# PM_HDMI_CON.net
KiCad netlist of a schematic drawn in Altium Designer
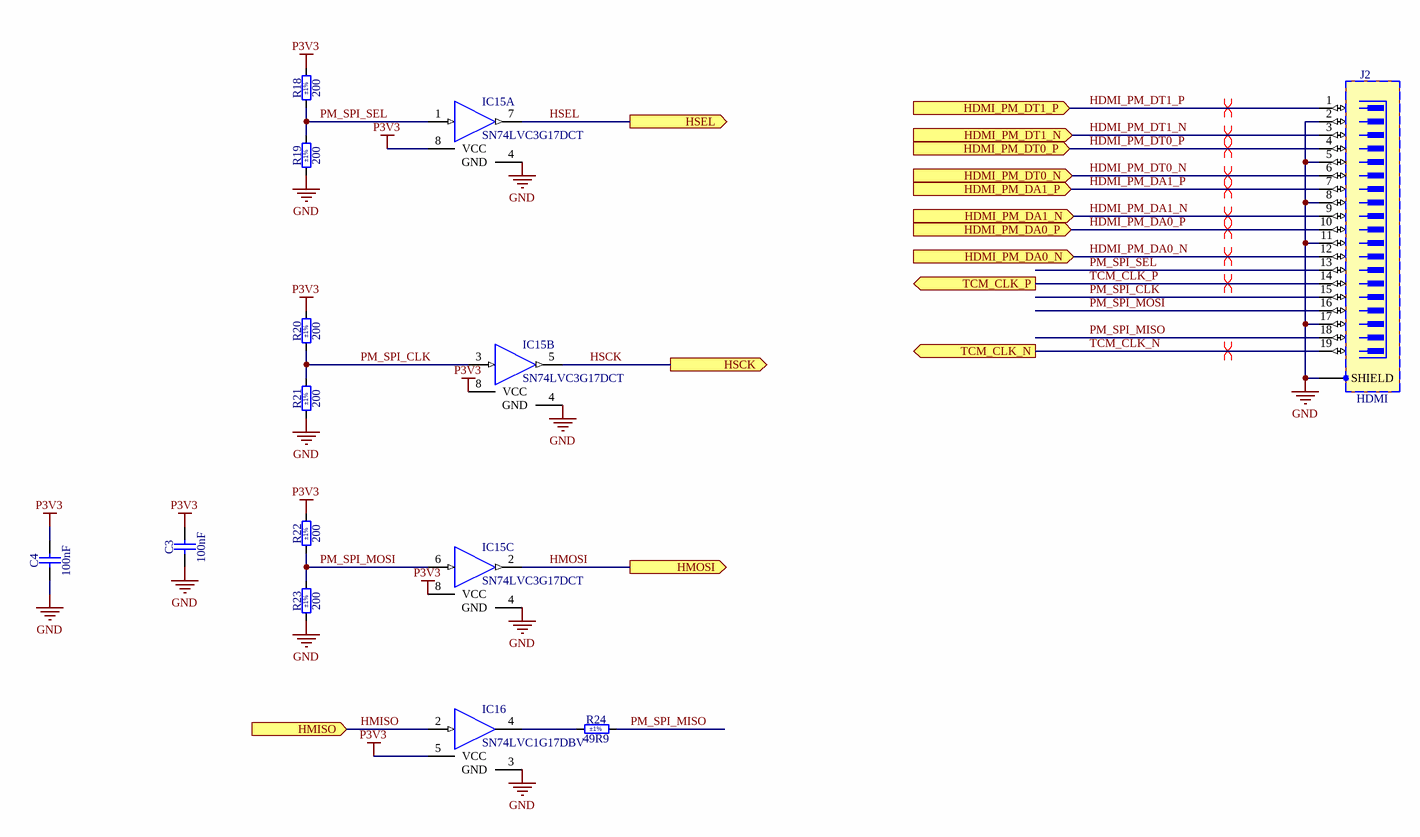
[diagram p0: PM_HDMI_CON.SchDoc]

(export (version "E")
  (design (tool "Eeschema 10.0.6"))
  (components
    (comp (ref "C3")
      (value "100nF")
      (footprint "CAPC1005X55N")
      (description "Non-polarised capacitor")
      (fields
        (field (name "PART NUMBER") "CC0402_100NF_50V_10%_X7R")
        (field (name "VOLTAGE") "50V")
        (field (name "AUTHOR") "CERN DEM MR")
      )
      (libsource (lib "Capacitors") (part "Capacitor - non polarized"))
    )
    (comp (ref "C4")
      (value "100nF")
      (footprint "CAPC1005X55N")
      (description "Non-polarised capacitor")
      (fields
        (field (name "PART NUMBER") "CC0402_100NF_50V_10%_X7R")
        (field (name "VOLTAGE") "50V")
        (field (name "AUTHOR") "CERN DEM MR")
      )
      (libsource (lib "Capacitors") (part "Capacitor - non polarized"))
    )
    (comp (ref "IC15")
      (value "SN74LVC3G17DCT")
      (footprint "SOP65P400X130-8N")
      (description "Triple Schmitt-Trigger Buffer")
      (fields (field (name "MANUFACTURER") "TEXAS INSTRUMENTS") (field (name "AUTHOR") "CERN DEM HF"))
      (libsource (lib "ICs And Semiconductors") (part "743G17"))
    )
    (comp (ref "IC16")
      (value "SN74LVC1G17DBV")
      (footprint "SOT95P280X145-5N")
      (description "Single Schmitt-Trigger Buffer")
      (fields
        (field (name "PART NUMBER") "SN74LVC1G17DBVR")
        (field (name "MANUFACTURER") "TEXAS INSTRUMENTS")
        (field (name "AUTHOR") "CERN DEM JLC")
      )
      (libsource (lib "ICs And Semiconductors") (part "741G17"))
    )
    (comp (ref "J2")
      (value "HDMI")
      (footprint "TYCO_2007435-1")
      (description "Connector HDMI 19 Male + 1 Shield")
      (fields
        (field (name "PART NUMBER") "TYCO_2007435-1")
        (field (name "MANUFACTURER") "TYCO ELECTRONICS")
        (field (name "AUTHOR") "CERN DEM MR")
      )
      (libsource (lib "Connectors") (part "Connector HDMI 19 Male + 1 Shield"))
    )
    (comp (ref "R18")
      (value "200")
      (footprint "RESC1608X55N")
      (description "Resistor - 1%")
      (fields
        (field (name "TOLERANCE") "±1%")
        (field (name "PART NUMBER") "R0603_200R_1%_0.1W_100PPM")
        (field (name "POWER") "0.1W")
        (field (name "AUTHOR") "CERN DEM JLC")
      )
      (libsource (lib "Resistors") (part "Resistor - 1%"))
    )
    (comp (ref "R19")
      (value "200")
      (footprint "RESC1608X55N")
      (description "Resistor - 1%")
      (fields
        (field (name "TOLERANCE") "±1%")
        (field (name "PART NUMBER") "R0603_200R_1%_0.1W_100PPM")
        (field (name "POWER") "0.1W")
        (field (name "AUTHOR") "CERN DEM JLC")
      )
      (libsource (lib "Resistors") (part "Resistor - 1%"))
    )
    (comp (ref "R20")
      (value "200")
      (footprint "RESC1608X55N")
      (description "Resistor - 1%")
      (fields
        (field (name "TOLERANCE") "±1%")
        (field (name "PART NUMBER") "R0603_200R_1%_0.1W_100PPM")
        (field (name "POWER") "0.1W")
        (field (name "AUTHOR") "CERN DEM JLC")
      )
      (libsource (lib "Resistors") (part "Resistor - 1%"))
    )
    (comp (ref "R21")
      (value "200")
      (footprint "RESC1608X55N")
      (description "Resistor - 1%")
      (fields
        (field (name "TOLERANCE") "±1%")
        (field (name "PART NUMBER") "R0603_200R_1%_0.1W_100PPM")
        (field (name "POWER") "0.1W")
        (field (name "AUTHOR") "CERN DEM JLC")
      )
      (libsource (lib "Resistors") (part "Resistor - 1%"))
    )
    (comp (ref "R22")
      (value "200")
      (footprint "RESC1608X55N")
      (description "Resistor - 1%")
      (fields
        (field (name "TOLERANCE") "±1%")
        (field (name "PART NUMBER") "R0603_200R_1%_0.1W_100PPM")
        (field (name "POWER") "0.1W")
        (field (name "AUTHOR") "CERN DEM JLC")
      )
      (libsource (lib "Resistors") (part "Resistor - 1%"))
    )
    (comp (ref "R23")
      (value "200")
      (footprint "RESC1608X55N")
      (description "Resistor - 1%")
      (fields
        (field (name "TOLERANCE") "±1%")
        (field (name "PART NUMBER") "R0603_200R_1%_0.1W_100PPM")
        (field (name "POWER") "0.1W")
        (field (name "AUTHOR") "CERN DEM JLC")
      )
      (libsource (lib "Resistors") (part "Resistor - 1%"))
    )
    (comp (ref "R24")
      (value "49R9")
      (footprint "RESC1005X40N")
      (description "Resistor - 1%")
      (fields
        (field (name "TOLERANCE") "±1%")
        (field (name "PART NUMBER") "R0402_49R9_1%_0.0625W_100PPM")
        (field (name "POWER") "0.0625W")
        (field (name "AUTHOR") "CERN DEM JLC")
      )
      (libsource (lib "Resistors") (part "Resistor - 1%"))
    )
  )
  (nets
    (net (code "1") (name "/HDMI_PM_DA0_N") (class "Default")
      (node (ref "J2") (pin "12") (pinfunction "12_12") (pintype "bidirectional"))
    )
    (net (code "2") (name "/HDMI_PM_DA0_P") (class "Default")
      (node (ref "J2") (pin "10") (pinfunction "10_10") (pintype "bidirectional"))
    )
    (net (code "3") (name "/HDMI_PM_DA1_N") (class "Default")
      (node (ref "J2") (pin "9") (pinfunction "9_9") (pintype "bidirectional"))
    )
    (net (code "4") (name "/HDMI_PM_DA1_P") (class "Default")
      (node (ref "J2") (pin "7") (pinfunction "7_7") (pintype "bidirectional"))
    )
    (net (code "5") (name "/HDMI_PM_DT0_N") (class "Default")
      (node (ref "J2") (pin "6") (pinfunction "6_6") (pintype "bidirectional"))
    )
    (net (code "6") (name "/HDMI_PM_DT0_P") (class "Default")
      (node (ref "J2") (pin "4") (pinfunction "4_4") (pintype "bidirectional"))
    )
    (net (code "7") (name "/HDMI_PM_DT1_N") (class "Default")
      (node (ref "J2") (pin "3") (pinfunction "3_3") (pintype "bidirectional"))
    )
    (net (code "8") (name "/HDMI_PM_DT1_P") (class "Default")
      (node (ref "J2") (pin "1") (pinfunction "1_1") (pintype "bidirectional"))
    )
    (net (code "9") (name "/HMISO") (class "Default")
      (node (ref "IC16") (pin "2") (pinfunction "IN_2") (pintype "input"))
    )
    (net (code "10") (name "/HMOSI") (class "Default")
      (node (ref "IC15") (pin "2") (pinfunction "OUT_2") (pintype "output"))
    )
    (net (code "11") (name "/HSCK") (class "Default")
      (node (ref "IC15") (pin "5") (pinfunction "OUT_5") (pintype "output"))
    )
    (net (code "12") (name "/HSEL") (class "Default")
      (node (ref "IC15") (pin "7") (pinfunction "OUT_7") (pintype "output"))
    )
    (net (code "13") (name "/PM_SPI_CLK") (class "Default")
      (node (ref "IC15") (pin "3") (pinfunction "IN_3") (pintype "input"))
      (node (ref "J2") (pin "15") (pinfunction "15_15") (pintype "bidirectional"))
      (node (ref "R20") (pin "1") (pinfunction "1_1") (pintype "passive"))
      (node (ref "R21") (pin "2") (pinfunction "2_2") (pintype "passive"))
    )
    (net (code "14") (name "/PM_SPI_MISO") (class "Default")
      (node (ref "J2") (pin "18") (pinfunction "18_18") (pintype "bidirectional"))
      (node (ref "R24") (pin "2") (pinfunction "2_2") (pintype "passive"))
    )
    (net (code "15") (name "/PM_SPI_MOSI") (class "Default")
      (node (ref "IC15") (pin "6") (pinfunction "IN_6") (pintype "input"))
      (node (ref "J2") (pin "16") (pinfunction "16_16") (pintype "bidirectional"))
      (node (ref "R22") (pin "1") (pinfunction "1_1") (pintype "passive"))
      (node (ref "R23") (pin "2") (pinfunction "2_2") (pintype "passive"))
    )
    (net (code "16") (name "/PM_SPI_SEL") (class "Default")
      (node (ref "IC15") (pin "1") (pinfunction "IN_1") (pintype "input"))
      (node (ref "J2") (pin "13") (pinfunction "13_13") (pintype "bidirectional"))
      (node (ref "R18") (pin "1") (pinfunction "1_1") (pintype "passive"))
      (node (ref "R19") (pin "2") (pinfunction "2_2") (pintype "passive"))
    )
    (net (code "17") (name "/TCM_CLK_N") (class "Default")
      (node (ref "J2") (pin "19") (pinfunction "19_19") (pintype "bidirectional"))
    )
    (net (code "18") (name "/TCM_CLK_P") (class "Default")
      (node (ref "J2") (pin "14") (pinfunction "14_14") (pintype "bidirectional"))
    )
    (net (code "19") (name "GND") (class "Default")
      (node (ref "C3") (pin "1") (pinfunction "1_1") (pintype "passive"))
      (node (ref "C4") (pin "1") (pinfunction "1_1") (pintype "passive"))
      (node (ref "IC15") (pin "4") (pinfunction "GND_4") (pintype "power_in"))
      (node (ref "IC16") (pin "3") (pinfunction "GND_3") (pintype "power_in"))
      (node (ref "J2") (pin "11") (pinfunction "11_11") (pintype "bidirectional"))
      (node (ref "J2") (pin "17") (pinfunction "17_17") (pintype "bidirectional"))
      (node (ref "J2") (pin "2") (pinfunction "2_2") (pintype "bidirectional"))
      (node (ref "J2") (pin "5") (pinfunction "5_5") (pintype "bidirectional"))
      (node (ref "J2") (pin "8") (pinfunction "8_8") (pintype "bidirectional"))
      (node (ref "J2") (pin "SHIELD") (pinfunction "SHIELD_SHIELD") (pintype "power_in"))
      (node (ref "R19") (pin "1") (pinfunction "1_1") (pintype "passive"))
      (node (ref "R21") (pin "1") (pinfunction "1_1") (pintype "passive"))
      (node (ref "R23") (pin "1") (pinfunction "1_1") (pintype "passive"))
    )
    (net (code "20") (name "Net-(IC16-OUT)") (class "Default")
      (node (ref "IC16") (pin "4") (pinfunction "OUT_4") (pintype "open_collector"))
      (node (ref "R24") (pin "1") (pinfunction "1_1") (pintype "passive"))
    )
    (net (code "21") (name "P3V3") (class "Default")
      (node (ref "C3") (pin "2") (pinfunction "2_2") (pintype "passive"))
      (node (ref "C4") (pin "2") (pinfunction "2_2") (pintype "passive"))
      (node (ref "IC15") (pin "8") (pinfunction "VCC_8") (pintype "power_in"))
      (node (ref "IC16") (pin "5") (pinfunction "VCC_5") (pintype "power_in"))
      (node (ref "R18") (pin "2") (pinfunction "2_2") (pintype "passive"))
      (node (ref "R20") (pin "2") (pinfunction "2_2") (pintype "passive"))
      (node (ref "R22") (pin "2") (pinfunction "2_2") (pintype "passive"))
    )
  )
)
